# HotRod.net
KiCad netlist of a schematic drawn in EAGLE
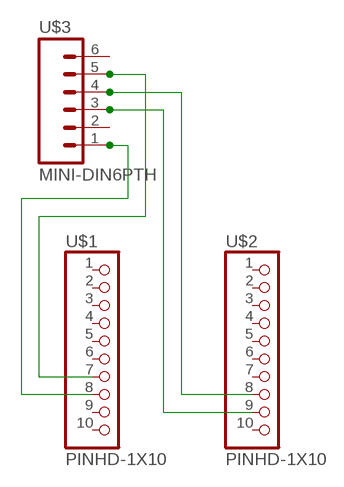
[diagram p0: schematic, sheet 1]

(export (version "E")
  (design (tool "Eeschema 10.0.6"))
  (components
    (comp (ref "U$1")
      (value "PINHD-1X10")
      (footprint "eagle-import:1X10-BIG")
      (libsource (lib "eagle-import") (part "PINHD-1X10"))
    )
    (comp (ref "U$2")
      (value "PINHD-1X10")
      (footprint "eagle-import:1X10-BIG")
      (libsource (lib "eagle-import") (part "PINHD-1X10"))
    )
    (comp (ref "U$3")
      (value "MINI-DIN6PTH")
      (footprint "eagle-import:MINI-DIN6")
      (libsource (lib "eagle-import") (part "MINI-DIN6PTH"))
    )
  )
  (nets
    (net (code "1") (name "Net-(U$1-Pad7)") (class "Default")
      (node (ref "U$1") (pin "7") (pinfunction "7_7") (pintype "passive"))
      (node (ref "U$3") (pin "5") (pinfunction "5_5") (pintype "passive"))
    )
    (net (code "2") (name "Net-(U$1-Pad8)") (class "Default")
      (node (ref "U$1") (pin "8") (pinfunction "8_8") (pintype "passive"))
      (node (ref "U$3") (pin "1") (pinfunction "1_1") (pintype "passive"))
    )
    (net (code "3") (name "Net-(U$2-Pad8)") (class "Default")
      (node (ref "U$2") (pin "8") (pinfunction "8_8") (pintype "passive"))
      (node (ref "U$3") (pin "4") (pinfunction "4_4") (pintype "passive"))
    )
    (net (code "4") (name "Net-(U$2-Pad9)") (class "Default")
      (node (ref "U$2") (pin "9") (pinfunction "9_9") (pintype "passive"))
      (node (ref "U$3") (pin "3") (pinfunction "3_3") (pintype "passive"))
    )
    (net (code "5") (name "unconnected-(U$1-Pad1)") (class "Default")
      (node (ref "U$1") (pin "1") (pinfunction "1_1") (pintype "passive"))
    )
    (net (code "6") (name "unconnected-(U$1-Pad2)") (class "Default")
      (node (ref "U$1") (pin "2") (pinfunction "2_2") (pintype "passive"))
    )
    (net (code "7") (name "unconnected-(U$1-Pad3)") (class "Default")
      (node (ref "U$1") (pin "3") (pinfunction "3_3") (pintype "passive"))
    )
    (net (code "8") (name "unconnected-(U$1-Pad4)") (class "Default")
      (node (ref "U$1") (pin "4") (pinfunction "4_4") (pintype "passive"))
    )
    (net (code "9") (name "unconnected-(U$1-Pad5)") (class "Default")
      (node (ref "U$1") (pin "5") (pinfunction "5_5") (pintype "passive"))
    )
    (net (code "10") (name "unconnected-(U$1-Pad6)") (class "Default")
      (node (ref "U$1") (pin "6") (pinfunction "6_6") (pintype "passive"))
    )
    (net (code "11") (name "unconnected-(U$1-Pad9)") (class "Default")
      (node (ref "U$1") (pin "9") (pinfunction "9_9") (pintype "passive"))
    )
    (net (code "12") (name "unconnected-(U$1-Pad10)") (class "Default")
      (node (ref "U$1") (pin "10") (pinfunction "10_10") (pintype "passive"))
    )
    (net (code "13") (name "unconnected-(U$2-Pad1)") (class "Default")
      (node (ref "U$2") (pin "1") (pinfunction "1_1") (pintype "passive"))
    )
    (net (code "14") (name "unconnected-(U$2-Pad2)") (class "Default")
      (node (ref "U$2") (pin "2") (pinfunction "2_2") (pintype "passive"))
    )
    (net (code "15") (name "unconnected-(U$2-Pad3)") (class "Default")
      (node (ref "U$2") (pin "3") (pinfunction "3_3") (pintype "passive"))
    )
    (net (code "16") (name "unconnected-(U$2-Pad4)") (class "Default")
      (node (ref "U$2") (pin "4") (pinfunction "4_4") (pintype "passive"))
    )
    (net (code "17") (name "unconnected-(U$2-Pad5)") (class "Default")
      (node (ref "U$2") (pin "5") (pinfunction "5_5") (pintype "passive"))
    )
    (net (code "18") (name "unconnected-(U$2-Pad6)") (class "Default")
      (node (ref "U$2") (pin "6") (pinfunction "6_6") (pintype "passive"))
    )
    (net (code "19") (name "unconnected-(U$2-Pad7)") (class "Default")
      (node (ref "U$2") (pin "7") (pinfunction "7_7") (pintype "passive"))
    )
    (net (code "20") (name "unconnected-(U$2-Pad10)") (class "Default")
      (node (ref "U$2") (pin "10") (pinfunction "10_10") (pintype "passive"))
    )
    (net (code "21") (name "unconnected-(U$3-Pad2)") (class "Default")
      (node (ref "U$3") (pin "2") (pinfunction "2_2") (pintype "passive"))
    )
    (net (code "22") (name "unconnected-(U$3-Pad6)") (class "Default")
      (node (ref "U$3") (pin "6") (pinfunction "6_6") (pintype "passive"))
    )
  )
)
